# B2xx_TRSwitch_A.net
KiCad netlist of a schematic drawn in EAGLE
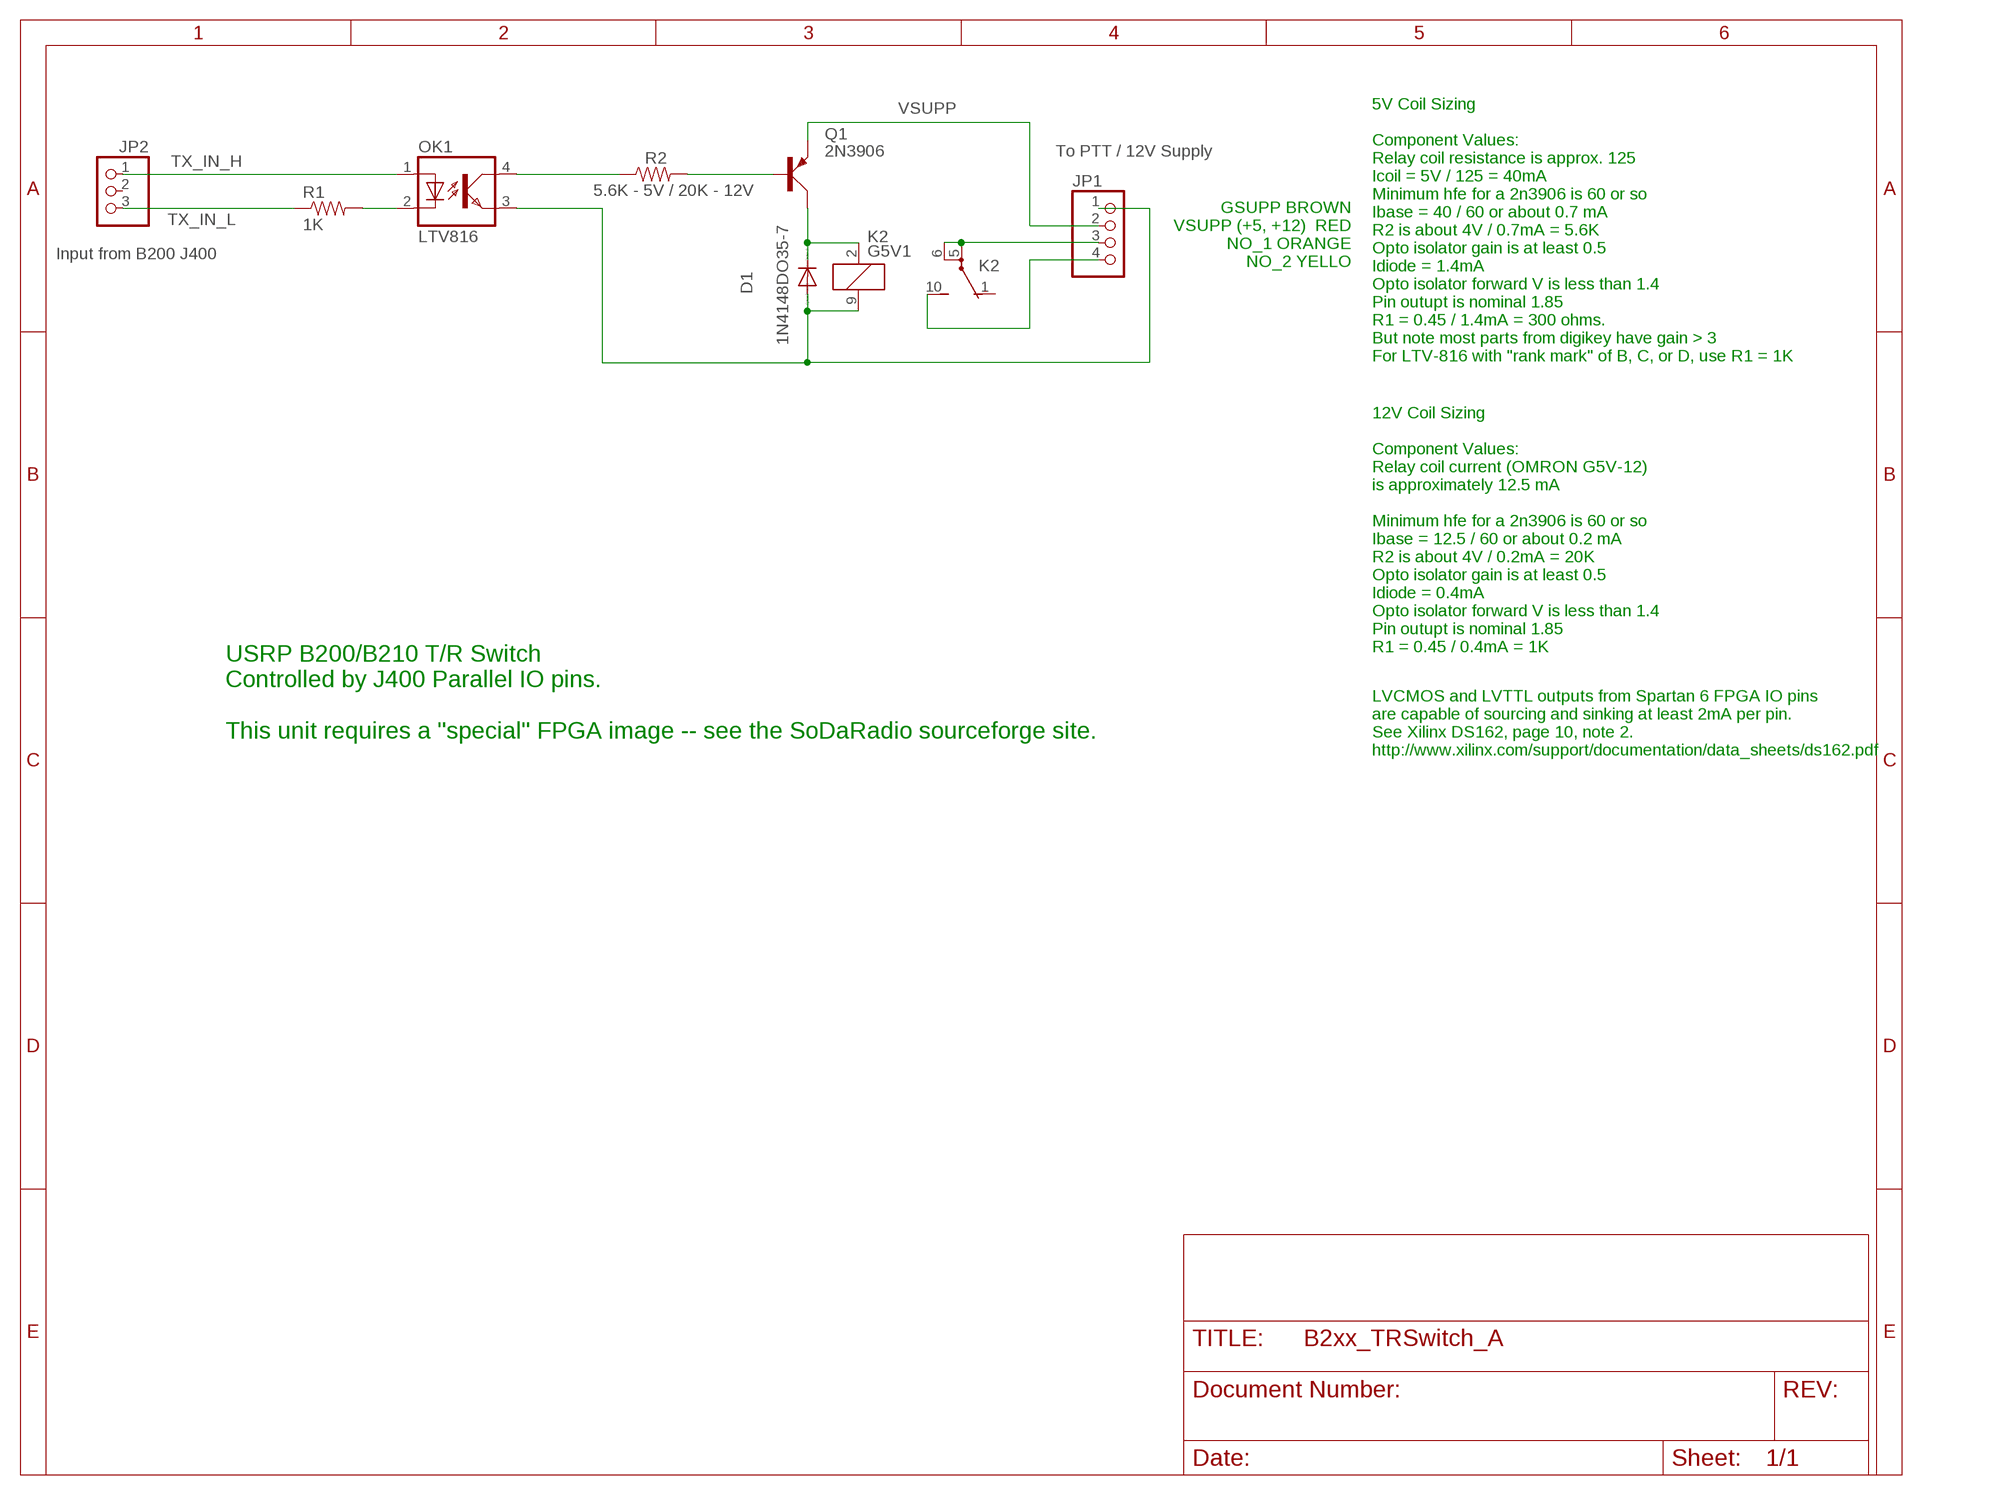
[diagram p0: schematic, sheet 1]

(export (version "E")
  (design (tool "Eeschema 10.0.6"))
  (components
    (comp (ref "D1")
      (value "1N4148DO35-7")
      (footprint "eagle-import:DO35-7")
      (libsource (lib "eagle-import") (part "1N4148DO35-7"))
    )
    (comp (ref "JP1")
      (value "To PTT / 12V Supply")
      (footprint "eagle-import:1X04")
      (libsource (lib "eagle-import") (part "PINHD-1X4"))
    )
    (comp (ref "JP2")
      (value "Input from B200 J400")
      (footprint "eagle-import:1X03")
      (libsource (lib "eagle-import") (part "PINHD-1X3"))
    )
    (comp (ref "K2")
      (value "G5V1")
      (footprint "eagle-import:G5V1")
      (fields (field (name "MPN") "G5V-1-DC24"))
      (libsource (lib "eagle-import") (part "G5V1"))
    )
    (comp (ref "OK1")
      (value "LTV816")
      (footprint "eagle-import:DIL04")
      (libsource (lib "eagle-import") (part "LTV816"))
    )
    (comp (ref "Q1")
      (value "2N3906")
      (footprint "eagle-import:TO92D")
      (libsource (lib "eagle-import") (part "2N3906"))
    )
    (comp (ref "R1")
      (value "1K")
      (footprint "eagle-import:AXIAL-0.3")
      (libsource (lib "eagle-import") (part "RESISTORAXIAL-0.3"))
    )
    (comp (ref "R2")
      (value "5.6K - 5V / 20K - 12V")
      (footprint "eagle-import:AXIAL-0.3")
      (libsource (lib "eagle-import") (part "RESISTORAXIAL-0.3"))
    )
  )
  (nets
    (net (code "1") (name "/TX_IN_H") (class "Default")
      (node (ref "JP2") (pin "1") (pinfunction "1_1") (pintype "passive"))
      (node (ref "OK1") (pin "1") (pinfunction "A_1") (pintype "passive"))
    )
    (net (code "2") (name "/TX_IN_L") (class "Default")
      (node (ref "JP2") (pin "3") (pinfunction "3_3") (pintype "passive"))
      (node (ref "R1") (pin "P$1") (pinfunction "1_P$1") (pintype "passive"))
    )
    (net (code "3") (name "/VSUPP") (class "Default")
      (node (ref "JP1") (pin "2") (pinfunction "2_2") (pintype "passive"))
      (node (ref "Q1") (pin "E") (pinfunction "E_E") (pintype "passive"))
    )
    (net (code "4") (name "Net-(JP1-Pad3)") (class "Default")
      (node (ref "JP1") (pin "3") (pinfunction "3_3") (pintype "passive"))
      (node (ref "K2") (pin "5") (pinfunction "P_5") (pintype "passive"))
      (node (ref "K2") (pin "6") (pinfunction "P_6") (pintype "passive"))
    )
    (net (code "5") (name "Net-(K2A-1)") (class "Default")
      (node (ref "D1") (pin "C") (pinfunction "C_C") (pintype "passive"))
      (node (ref "K2") (pin "2") (pinfunction "1_2") (pintype "passive"))
      (node (ref "Q1") (pin "C") (pinfunction "C_C") (pintype "passive"))
    )
    (net (code "6") (name "Net-(K2A-2)") (class "Default")
      (node (ref "D1") (pin "A") (pinfunction "A_A") (pintype "passive"))
      (node (ref "JP1") (pin "1") (pinfunction "1_1") (pintype "passive"))
      (node (ref "K2") (pin "9") (pinfunction "2_9") (pintype "passive"))
      (node (ref "OK1") (pin "3") (pinfunction "EMIT_3") (pintype "passive"))
    )
    (net (code "7") (name "Net-(K2B-S)") (class "Default")
      (node (ref "JP1") (pin "4") (pinfunction "4_4") (pintype "passive"))
      (node (ref "K2") (pin "10") (pinfunction "S_10") (pintype "passive"))
    )
    (net (code "8") (name "Net-(OK1-C)") (class "Default")
      (node (ref "OK1") (pin "2") (pinfunction "C_2") (pintype "passive"))
      (node (ref "R1") (pin "P$2") (pinfunction "2_P$2") (pintype "passive"))
    )
    (net (code "9") (name "Net-(OK1-COL)") (class "Default")
      (node (ref "OK1") (pin "4") (pinfunction "COL_4") (pintype "passive"))
      (node (ref "R2") (pin "P$1") (pinfunction "1_P$1") (pintype "passive"))
    )
    (net (code "10") (name "Net-(R2-2)") (class "Default")
      (node (ref "Q1") (pin "B") (pinfunction "B_B") (pintype "passive"))
      (node (ref "R2") (pin "P$2") (pinfunction "2_P$2") (pintype "passive"))
    )
    (net (code "11") (name "unconnected-(JP2-Pad2)") (class "Default")
      (node (ref "JP2") (pin "2") (pinfunction "2_2") (pintype "passive"))
    )
    (net (code "12") (name "unconnected-(K2B-O-Pad1)") (class "Default")
      (node (ref "K2") (pin "1") (pinfunction "O_1") (pintype "passive"))
    )
  )
)
